# Peliminary_board.net
KiCad netlist of a schematic drawn in EAGLE
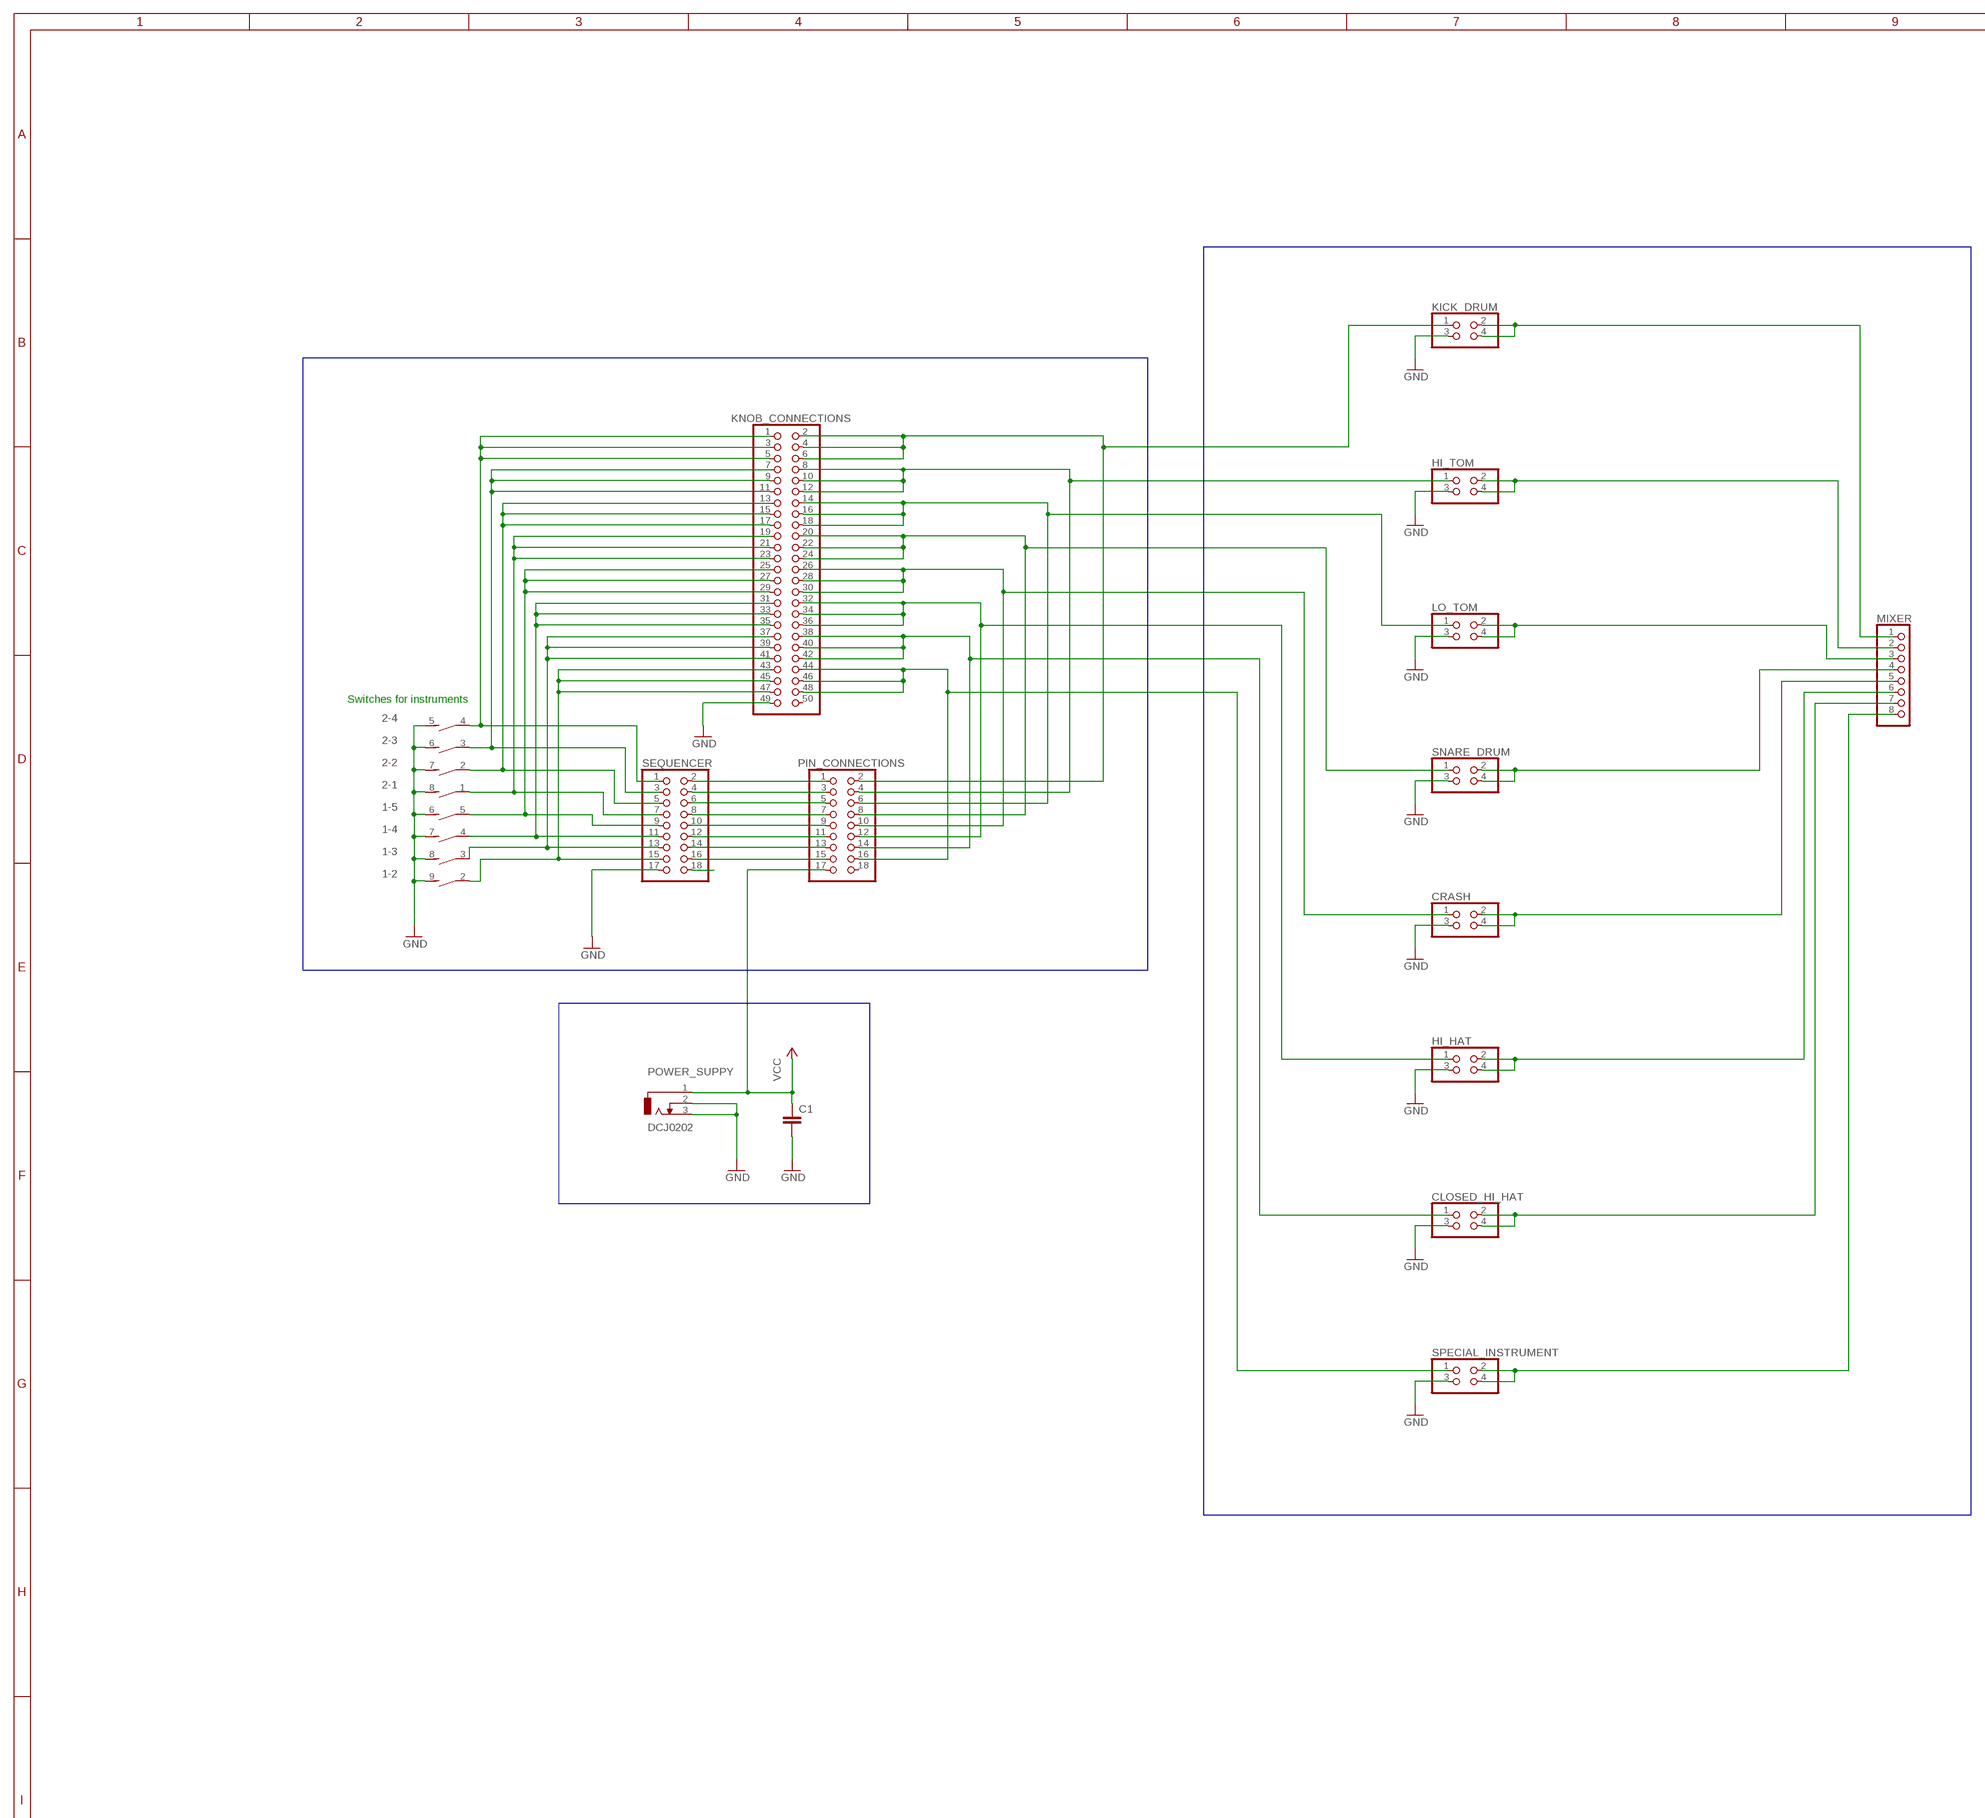
[diagram p0: schematic, sheet 1, part 1 of 2]
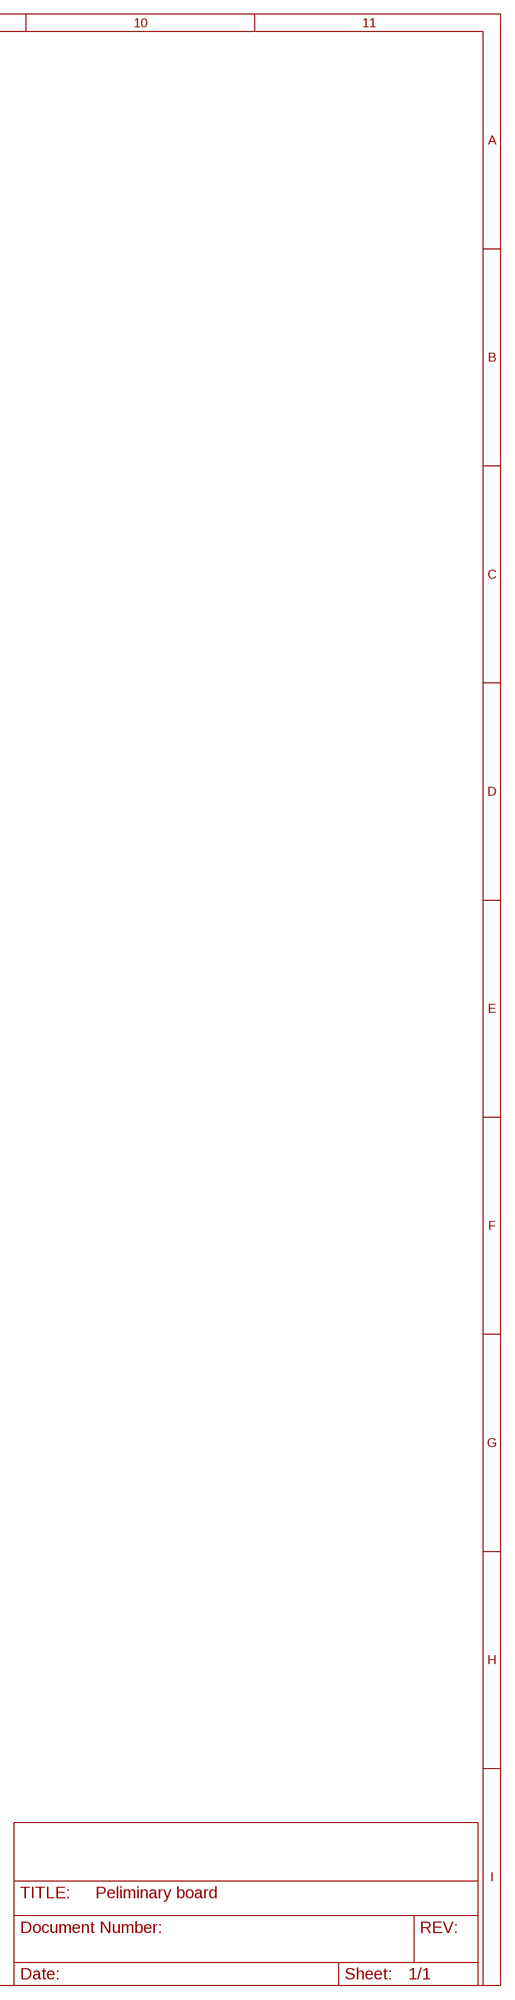
[diagram p1: schematic, sheet 1, part 2 of 2]

(export (version "E")
  (design (tool "Eeschema 10.0.6"))
  (components
    (comp (ref "1")
      (value "DS05E")
      (footprint "eagle-import:DS-05")
      (libsource (lib "eagle-import") (part "DS05E"))
    )
    (comp (ref "2")
      (value "DIP04S")
      (footprint "eagle-import:DIP04S")
      (libsource (lib "eagle-import") (part "DIP04S"))
    )
    (comp (ref "C1")
      (value "C2,5-3")
      (footprint "eagle-import:C2.5-3")
      (libsource (lib "eagle-import") (part "C2,5-3"))
    )
    (comp (ref "CLOSED_HI_HAT")
      (value "PINHD-2X2")
      (footprint "eagle-import:2X02")
      (libsource (lib "eagle-import") (part "PINHD-2X2"))
    )
    (comp (ref "CRASH")
      (value "PINHD-2X2")
      (footprint "eagle-import:2X02")
      (libsource (lib "eagle-import") (part "PINHD-2X2"))
    )
    (comp (ref "HI_HAT")
      (value "PINHD-2X2")
      (footprint "eagle-import:2X02")
      (libsource (lib "eagle-import") (part "PINHD-2X2"))
    )
    (comp (ref "HI_TOM")
      (value "PINHD-2X2")
      (footprint "eagle-import:2X02")
      (libsource (lib "eagle-import") (part "PINHD-2X2"))
    )
    (comp (ref "KICK_DRUM")
      (value "PINHD-2X2")
      (footprint "eagle-import:2X02")
      (libsource (lib "eagle-import") (part "PINHD-2X2"))
    )
    (comp (ref "KNOB_CONNECTIONS")
      (value "PINHD-2X25")
      (footprint "eagle-import:2X25")
      (libsource (lib "eagle-import") (part "PINHD-2X25"))
    )
    (comp (ref "LO_TOM")
      (value "PINHD-2X2")
      (footprint "eagle-import:2X02")
      (libsource (lib "eagle-import") (part "PINHD-2X2"))
    )
    (comp (ref "MIXER")
      (value "PINHD-1X8")
      (footprint "eagle-import:1X08")
      (libsource (lib "eagle-import") (part "PINHD-1X8"))
    )
    (comp (ref "PIN_CONNECTIONS")
      (value "PINHD-2X9")
      (footprint "eagle-import:2X09")
      (libsource (lib "eagle-import") (part "PINHD-2X9"))
    )
    (comp (ref "POWER_SUPPY")
      (value "DCJ0202")
      (footprint "eagle-import:DCJ0202")
      (libsource (lib "eagle-import") (part "DCJ0202"))
    )
    (comp (ref "SEQUENCER")
      (value "PINHD-2X9")
      (footprint "eagle-import:2X09")
      (libsource (lib "eagle-import") (part "PINHD-2X9"))
    )
    (comp (ref "SNARE_DRUM")
      (value "PINHD-2X2")
      (footprint "eagle-import:2X02")
      (libsource (lib "eagle-import") (part "PINHD-2X2"))
    )
    (comp (ref "SPECIAL_INSTRUMENT")
      (value "PINHD-2X2")
      (footprint "eagle-import:2X02")
      (libsource (lib "eagle-import") (part "PINHD-2X2"))
    )
  )
  (nets
    (net (code "1") (name "GND") (class "Default")
      (node (ref "1") (pin "6") (pinfunction "2_6") (pintype "passive"))
      (node (ref "1") (pin "7") (pinfunction "2_7") (pintype "passive"))
      (node (ref "1") (pin "8") (pinfunction "2_8") (pintype "passive"))
      (node (ref "1") (pin "9") (pinfunction "2_9") (pintype "passive"))
      (node (ref "2") (pin "5") (pinfunction "2_5") (pintype "passive"))
      (node (ref "2") (pin "6") (pinfunction "2_6") (pintype "passive"))
      (node (ref "2") (pin "7") (pinfunction "2_7") (pintype "passive"))
      (node (ref "2") (pin "8") (pinfunction "2_8") (pintype "passive"))
      (node (ref "C1") (pin "2") (pinfunction "2_2") (pintype "passive"))
      (node (ref "CLOSED_HI_HAT") (pin "3") (pinfunction "3_3") (pintype "passive"))
      (node (ref "CRASH") (pin "3") (pinfunction "3_3") (pintype "passive"))
      (node (ref "HI_HAT") (pin "3") (pinfunction "3_3") (pintype "passive"))
      (node (ref "HI_TOM") (pin "3") (pinfunction "3_3") (pintype "passive"))
      (node (ref "KICK_DRUM") (pin "3") (pinfunction "3_3") (pintype "passive"))
      (node (ref "KNOB_CONNECTIONS") (pin "49") (pinfunction "49_49") (pintype "passive"))
      (node (ref "LO_TOM") (pin "3") (pinfunction "3_3") (pintype "passive"))
      (node (ref "POWER_SUPPY") (pin "2") (pinfunction "2_2") (pintype "passive"))
      (node (ref "POWER_SUPPY") (pin "3") (pinfunction "3_3") (pintype "passive"))
      (node (ref "SEQUENCER") (pin "17") (pinfunction "17_17") (pintype "passive"))
      (node (ref "SNARE_DRUM") (pin "3") (pinfunction "3_3") (pintype "passive"))
      (node (ref "SPECIAL_INSTRUMENT") (pin "3") (pinfunction "3_3") (pintype "passive"))
    )
    (net (code "2") (name "Net-(1B-1)") (class "Default")
      (node (ref "1") (pin "2") (pinfunction "1_2") (pintype "passive"))
      (node (ref "KNOB_CONNECTIONS") (pin "43") (pinfunction "43_43") (pintype "passive"))
      (node (ref "KNOB_CONNECTIONS") (pin "45") (pinfunction "45_45") (pintype "passive"))
      (node (ref "KNOB_CONNECTIONS") (pin "47") (pinfunction "47_47") (pintype "passive"))
      (node (ref "SEQUENCER") (pin "15") (pinfunction "15_15") (pintype "passive"))
    )
    (net (code "3") (name "Net-(1C-1)") (class "Default")
      (node (ref "1") (pin "3") (pinfunction "1_3") (pintype "passive"))
      (node (ref "KNOB_CONNECTIONS") (pin "37") (pinfunction "37_37") (pintype "passive"))
      (node (ref "KNOB_CONNECTIONS") (pin "39") (pinfunction "39_39") (pintype "passive"))
      (node (ref "KNOB_CONNECTIONS") (pin "41") (pinfunction "41_41") (pintype "passive"))
      (node (ref "SEQUENCER") (pin "13") (pinfunction "13_13") (pintype "passive"))
    )
    (net (code "4") (name "Net-(1D-1)") (class "Default")
      (node (ref "1") (pin "4") (pinfunction "1_4") (pintype "passive"))
      (node (ref "KNOB_CONNECTIONS") (pin "31") (pinfunction "31_31") (pintype "passive"))
      (node (ref "KNOB_CONNECTIONS") (pin "33") (pinfunction "33_33") (pintype "passive"))
      (node (ref "KNOB_CONNECTIONS") (pin "35") (pinfunction "35_35") (pintype "passive"))
      (node (ref "SEQUENCER") (pin "11") (pinfunction "11_11") (pintype "passive"))
    )
    (net (code "5") (name "Net-(1E-1)") (class "Default")
      (node (ref "1") (pin "5") (pinfunction "1_5") (pintype "passive"))
      (node (ref "KNOB_CONNECTIONS") (pin "25") (pinfunction "25_25") (pintype "passive"))
      (node (ref "KNOB_CONNECTIONS") (pin "27") (pinfunction "27_27") (pintype "passive"))
      (node (ref "KNOB_CONNECTIONS") (pin "29") (pinfunction "29_29") (pintype "passive"))
      (node (ref "SEQUENCER") (pin "9") (pinfunction "9_9") (pintype "passive"))
    )
    (net (code "6") (name "Net-(2-Pad1)") (class "Default")
      (node (ref "2") (pin "1") (pinfunction "1_1") (pintype "passive"))
      (node (ref "KNOB_CONNECTIONS") (pin "19") (pinfunction "19_19") (pintype "passive"))
      (node (ref "KNOB_CONNECTIONS") (pin "21") (pinfunction "21_21") (pintype "passive"))
      (node (ref "KNOB_CONNECTIONS") (pin "23") (pinfunction "23_23") (pintype "passive"))
      (node (ref "SEQUENCER") (pin "7") (pinfunction "7_7") (pintype "passive"))
    )
    (net (code "7") (name "Net-(2B-1)") (class "Default")
      (node (ref "2") (pin "2") (pinfunction "1_2") (pintype "passive"))
      (node (ref "KNOB_CONNECTIONS") (pin "13") (pinfunction "13_13") (pintype "passive"))
      (node (ref "KNOB_CONNECTIONS") (pin "15") (pinfunction "15_15") (pintype "passive"))
      (node (ref "KNOB_CONNECTIONS") (pin "17") (pinfunction "17_17") (pintype "passive"))
      (node (ref "SEQUENCER") (pin "5") (pinfunction "5_5") (pintype "passive"))
    )
    (net (code "8") (name "Net-(2C-1)") (class "Default")
      (node (ref "2") (pin "3") (pinfunction "1_3") (pintype "passive"))
      (node (ref "KNOB_CONNECTIONS") (pin "11") (pinfunction "11_11") (pintype "passive"))
      (node (ref "KNOB_CONNECTIONS") (pin "7") (pinfunction "7_7") (pintype "passive"))
      (node (ref "KNOB_CONNECTIONS") (pin "9") (pinfunction "9_9") (pintype "passive"))
      (node (ref "SEQUENCER") (pin "3") (pinfunction "3_3") (pintype "passive"))
    )
    (net (code "9") (name "Net-(2D-1)") (class "Default")
      (node (ref "2") (pin "4") (pinfunction "1_4") (pintype "passive"))
      (node (ref "KNOB_CONNECTIONS") (pin "1") (pinfunction "1_1") (pintype "passive"))
      (node (ref "KNOB_CONNECTIONS") (pin "3") (pinfunction "3_3") (pintype "passive"))
      (node (ref "KNOB_CONNECTIONS") (pin "5") (pinfunction "5_5") (pintype "passive"))
      (node (ref "SEQUENCER") (pin "1") (pinfunction "1_1") (pintype "passive"))
    )
    (net (code "10") (name "Net-(CLOSED_HI_HAT-Pad1)") (class "Default")
      (node (ref "CLOSED_HI_HAT") (pin "1") (pinfunction "1_1") (pintype "passive"))
      (node (ref "KNOB_CONNECTIONS") (pin "38") (pinfunction "38_38") (pintype "passive"))
      (node (ref "KNOB_CONNECTIONS") (pin "40") (pinfunction "40_40") (pintype "passive"))
      (node (ref "KNOB_CONNECTIONS") (pin "42") (pinfunction "42_42") (pintype "passive"))
      (node (ref "PIN_CONNECTIONS") (pin "14") (pinfunction "14_14") (pintype "passive"))
    )
    (net (code "11") (name "Net-(CLOSED_HI_HAT-Pad2)") (class "Default")
      (node (ref "CLOSED_HI_HAT") (pin "2") (pinfunction "2_2") (pintype "passive"))
      (node (ref "CLOSED_HI_HAT") (pin "4") (pinfunction "4_4") (pintype "passive"))
      (node (ref "MIXER") (pin "7") (pinfunction "7_7") (pintype "passive"))
    )
    (net (code "12") (name "Net-(CRASH-Pad1)") (class "Default")
      (node (ref "CRASH") (pin "1") (pinfunction "1_1") (pintype "passive"))
      (node (ref "KNOB_CONNECTIONS") (pin "26") (pinfunction "26_26") (pintype "passive"))
      (node (ref "KNOB_CONNECTIONS") (pin "28") (pinfunction "28_28") (pintype "passive"))
      (node (ref "KNOB_CONNECTIONS") (pin "30") (pinfunction "30_30") (pintype "passive"))
      (node (ref "PIN_CONNECTIONS") (pin "10") (pinfunction "10_10") (pintype "passive"))
    )
    (net (code "13") (name "Net-(CRASH-Pad2)") (class "Default")
      (node (ref "CRASH") (pin "2") (pinfunction "2_2") (pintype "passive"))
      (node (ref "CRASH") (pin "4") (pinfunction "4_4") (pintype "passive"))
      (node (ref "MIXER") (pin "5") (pinfunction "5_5") (pintype "passive"))
    )
    (net (code "14") (name "Net-(HI_HAT-Pad1)") (class "Default")
      (node (ref "HI_HAT") (pin "1") (pinfunction "1_1") (pintype "passive"))
      (node (ref "KNOB_CONNECTIONS") (pin "32") (pinfunction "32_32") (pintype "passive"))
      (node (ref "KNOB_CONNECTIONS") (pin "34") (pinfunction "34_34") (pintype "passive"))
      (node (ref "KNOB_CONNECTIONS") (pin "36") (pinfunction "36_36") (pintype "passive"))
      (node (ref "PIN_CONNECTIONS") (pin "12") (pinfunction "12_12") (pintype "passive"))
    )
    (net (code "15") (name "Net-(HI_HAT-Pad2)") (class "Default")
      (node (ref "HI_HAT") (pin "2") (pinfunction "2_2") (pintype "passive"))
      (node (ref "HI_HAT") (pin "4") (pinfunction "4_4") (pintype "passive"))
      (node (ref "MIXER") (pin "6") (pinfunction "6_6") (pintype "passive"))
    )
    (net (code "16") (name "Net-(HI_TOM-Pad1)") (class "Default")
      (node (ref "HI_TOM") (pin "1") (pinfunction "1_1") (pintype "passive"))
      (node (ref "KNOB_CONNECTIONS") (pin "10") (pinfunction "10_10") (pintype "passive"))
      (node (ref "KNOB_CONNECTIONS") (pin "12") (pinfunction "12_12") (pintype "passive"))
      (node (ref "KNOB_CONNECTIONS") (pin "8") (pinfunction "8_8") (pintype "passive"))
      (node (ref "PIN_CONNECTIONS") (pin "4") (pinfunction "4_4") (pintype "passive"))
    )
    (net (code "17") (name "Net-(HI_TOM-Pad2)") (class "Default")
      (node (ref "HI_TOM") (pin "2") (pinfunction "2_2") (pintype "passive"))
      (node (ref "HI_TOM") (pin "4") (pinfunction "4_4") (pintype "passive"))
      (node (ref "MIXER") (pin "2") (pinfunction "2_2") (pintype "passive"))
    )
    (net (code "18") (name "Net-(KICK_DRUM-Pad1)") (class "Default")
      (node (ref "KICK_DRUM") (pin "1") (pinfunction "1_1") (pintype "passive"))
      (node (ref "KNOB_CONNECTIONS") (pin "2") (pinfunction "2_2") (pintype "passive"))
      (node (ref "KNOB_CONNECTIONS") (pin "4") (pinfunction "4_4") (pintype "passive"))
      (node (ref "KNOB_CONNECTIONS") (pin "6") (pinfunction "6_6") (pintype "passive"))
      (node (ref "PIN_CONNECTIONS") (pin "2") (pinfunction "2_2") (pintype "passive"))
    )
    (net (code "19") (name "Net-(KICK_DRUM-Pad2)") (class "Default")
      (node (ref "KICK_DRUM") (pin "2") (pinfunction "2_2") (pintype "passive"))
      (node (ref "KICK_DRUM") (pin "4") (pinfunction "4_4") (pintype "passive"))
      (node (ref "MIXER") (pin "1") (pinfunction "1_1") (pintype "passive"))
    )
    (net (code "20") (name "Net-(KNOB_CONNECTIONS-Pad14)") (class "Default")
      (node (ref "KNOB_CONNECTIONS") (pin "14") (pinfunction "14_14") (pintype "passive"))
      (node (ref "KNOB_CONNECTIONS") (pin "16") (pinfunction "16_16") (pintype "passive"))
      (node (ref "KNOB_CONNECTIONS") (pin "18") (pinfunction "18_18") (pintype "passive"))
      (node (ref "LO_TOM") (pin "1") (pinfunction "1_1") (pintype "passive"))
      (node (ref "PIN_CONNECTIONS") (pin "6") (pinfunction "6_6") (pintype "passive"))
    )
    (net (code "21") (name "Net-(KNOB_CONNECTIONS-Pad20)") (class "Default")
      (node (ref "KNOB_CONNECTIONS") (pin "20") (pinfunction "20_20") (pintype "passive"))
      (node (ref "KNOB_CONNECTIONS") (pin "22") (pinfunction "22_22") (pintype "passive"))
      (node (ref "KNOB_CONNECTIONS") (pin "24") (pinfunction "24_24") (pintype "passive"))
      (node (ref "PIN_CONNECTIONS") (pin "8") (pinfunction "8_8") (pintype "passive"))
      (node (ref "SNARE_DRUM") (pin "1") (pinfunction "1_1") (pintype "passive"))
    )
    (net (code "22") (name "Net-(KNOB_CONNECTIONS-Pad44)") (class "Default")
      (node (ref "KNOB_CONNECTIONS") (pin "44") (pinfunction "44_44") (pintype "passive"))
      (node (ref "KNOB_CONNECTIONS") (pin "46") (pinfunction "46_46") (pintype "passive"))
      (node (ref "KNOB_CONNECTIONS") (pin "48") (pinfunction "48_48") (pintype "passive"))
      (node (ref "PIN_CONNECTIONS") (pin "16") (pinfunction "16_16") (pintype "passive"))
      (node (ref "SPECIAL_INSTRUMENT") (pin "1") (pinfunction "1_1") (pintype "passive"))
    )
    (net (code "23") (name "Net-(LO_TOM-Pad2)") (class "Default")
      (node (ref "LO_TOM") (pin "2") (pinfunction "2_2") (pintype "passive"))
      (node (ref "LO_TOM") (pin "4") (pinfunction "4_4") (pintype "passive"))
      (node (ref "MIXER") (pin "3") (pinfunction "3_3") (pintype "passive"))
    )
    (net (code "24") (name "Net-(MIXER-Pad4)") (class "Default")
      (node (ref "MIXER") (pin "4") (pinfunction "4_4") (pintype "passive"))
      (node (ref "SNARE_DRUM") (pin "2") (pinfunction "2_2") (pintype "passive"))
      (node (ref "SNARE_DRUM") (pin "4") (pinfunction "4_4") (pintype "passive"))
    )
    (net (code "25") (name "Net-(MIXER-Pad8)") (class "Default")
      (node (ref "MIXER") (pin "8") (pinfunction "8_8") (pintype "passive"))
      (node (ref "SPECIAL_INSTRUMENT") (pin "2") (pinfunction "2_2") (pintype "passive"))
      (node (ref "SPECIAL_INSTRUMENT") (pin "4") (pinfunction "4_4") (pintype "passive"))
    )
    (net (code "26") (name "Net-(PIN_CONNECTIONS-Pad1)") (class "Default")
      (node (ref "PIN_CONNECTIONS") (pin "1") (pinfunction "1_1") (pintype "passive"))
      (node (ref "SEQUENCER") (pin "2") (pinfunction "2_2") (pintype "passive"))
    )
    (net (code "27") (name "Net-(PIN_CONNECTIONS-Pad3)") (class "Default")
      (node (ref "PIN_CONNECTIONS") (pin "3") (pinfunction "3_3") (pintype "passive"))
      (node (ref "SEQUENCER") (pin "4") (pinfunction "4_4") (pintype "passive"))
    )
    (net (code "28") (name "Net-(PIN_CONNECTIONS-Pad5)") (class "Default")
      (node (ref "PIN_CONNECTIONS") (pin "5") (pinfunction "5_5") (pintype "passive"))
      (node (ref "SEQUENCER") (pin "6") (pinfunction "6_6") (pintype "passive"))
    )
    (net (code "29") (name "Net-(PIN_CONNECTIONS-Pad7)") (class "Default")
      (node (ref "PIN_CONNECTIONS") (pin "7") (pinfunction "7_7") (pintype "passive"))
      (node (ref "SEQUENCER") (pin "8") (pinfunction "8_8") (pintype "passive"))
    )
    (net (code "30") (name "Net-(PIN_CONNECTIONS-Pad9)") (class "Default")
      (node (ref "PIN_CONNECTIONS") (pin "9") (pinfunction "9_9") (pintype "passive"))
      (node (ref "SEQUENCER") (pin "10") (pinfunction "10_10") (pintype "passive"))
    )
    (net (code "31") (name "Net-(PIN_CONNECTIONS-Pad11)") (class "Default")
      (node (ref "PIN_CONNECTIONS") (pin "11") (pinfunction "11_11") (pintype "passive"))
      (node (ref "SEQUENCER") (pin "12") (pinfunction "12_12") (pintype "passive"))
    )
    (net (code "32") (name "Net-(PIN_CONNECTIONS-Pad13)") (class "Default")
      (node (ref "PIN_CONNECTIONS") (pin "13") (pinfunction "13_13") (pintype "passive"))
      (node (ref "SEQUENCER") (pin "14") (pinfunction "14_14") (pintype "passive"))
    )
    (net (code "33") (name "Net-(PIN_CONNECTIONS-Pad15)") (class "Default")
      (node (ref "PIN_CONNECTIONS") (pin "15") (pinfunction "15_15") (pintype "passive"))
      (node (ref "SEQUENCER") (pin "16") (pinfunction "16_16") (pintype "passive"))
    )
    (net (code "34") (name "VCC") (class "Default")
      (node (ref "C1") (pin "1") (pinfunction "1_1") (pintype "passive"))
      (node (ref "PIN_CONNECTIONS") (pin "17") (pinfunction "17_17") (pintype "passive"))
      (node (ref "POWER_SUPPY") (pin "1") (pinfunction "1_1") (pintype "passive"))
    )
    (net (code "35") (name "unconnected-(KNOB_CONNECTIONS-Pad50)") (class "Default")
      (node (ref "KNOB_CONNECTIONS") (pin "50") (pinfunction "50_50") (pintype "passive"))
    )
    (net (code "36") (name "unconnected-(PIN_CONNECTIONS-Pad18)") (class "Default")
      (node (ref "PIN_CONNECTIONS") (pin "18") (pinfunction "18_18") (pintype "passive"))
    )
    (net (code "37") (name "unconnected-(SEQUENCER-Pad18)") (class "Default")
      (node (ref "SEQUENCER") (pin "18") (pinfunction "18_18") (pintype "passive"))
    )
  )
)
